# 07_MOTOR.net
KiCad netlist of a schematic drawn in Altium Designer
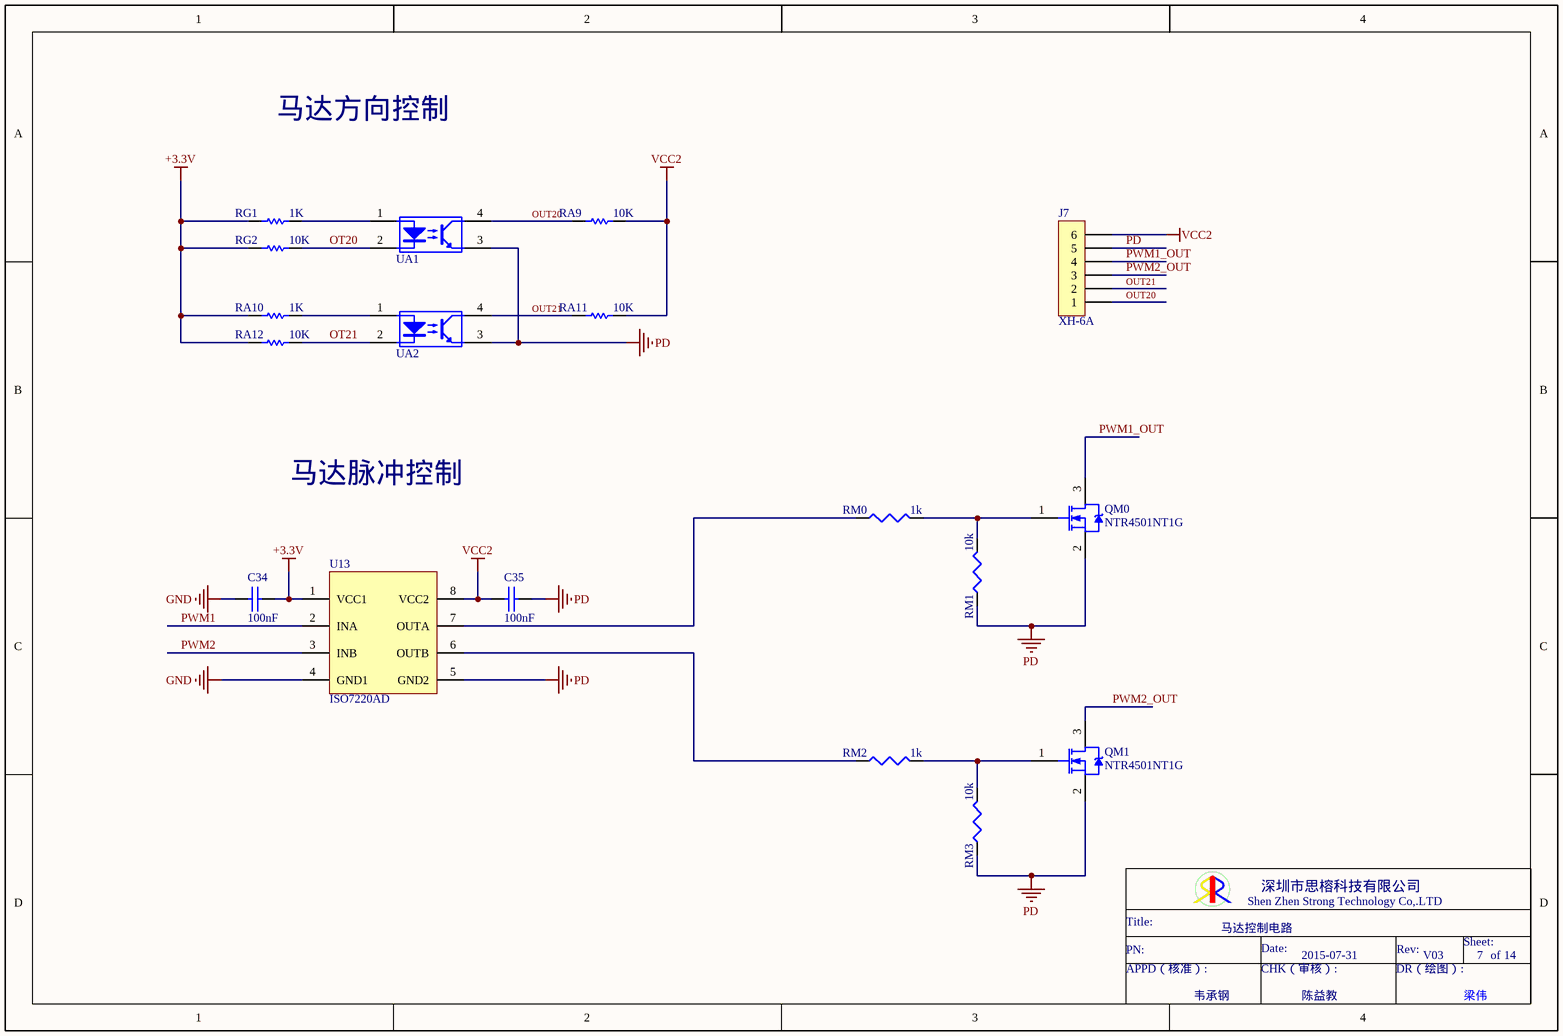
[diagram p0: 07_MOTOR.SchDoc]

(export (version "E")
  (design (tool "Eeschema 10.0.6"))
  (components
    (comp (ref "C34") (value "100nF") (footprint "0603C") (libsource (lib "WeiCHGSCH") (part "CAP")))
    (comp (ref "C35") (value "100nF") (footprint "0603C") (libsource (lib "WeiCHGSCH") (part "CAP")))
    (comp (ref "J7")
      (value "XH-6A")
      (footprint "CN6-2.54")
      (description "单排")
      (libsource (lib "Mylibrary") (part "CON6"))
    )
    (comp (ref "QM0")
      (value "NTR4501NT1G")
      (footprint "SOT23")
      (description "MOSFET N沟道")
      (libsource (lib "LGA") (part "MOSFET-N"))
    )
    (comp (ref "QM1")
      (value "NTR4501NT1G")
      (footprint "SOT23")
      (description "MOSFET N沟道")
      (libsource (lib "LGA") (part "MOSFET-N"))
    )
    (comp (ref "RA9") (value "10K") (footprint "0603R") (libsource (lib "Mylibrary") (part "RES")))
    (comp (ref "RA10") (value "1K") (footprint "0603R") (libsource (lib "Mylibrary") (part "RES")))
    (comp (ref "RA11") (value "10K") (footprint "0603R") (libsource (lib "Mylibrary") (part "RES")))
    (comp (ref "RA12") (value "10K") (footprint "0603R") (libsource (lib "Mylibrary") (part "RES")))
    (comp (ref "RG1") (value "1K") (footprint "0603R") (libsource (lib "Mylibrary") (part "RES")))
    (comp (ref "RG2") (value "10K") (footprint "0603R") (libsource (lib "Mylibrary") (part "RES")))
    (comp (ref "RM0") (value "1k") (footprint "0603R") (libsource (lib "LGA") (part "RES1")))
    (comp (ref "RM1") (value "10k") (footprint "0603R") (libsource (lib "LGA") (part "RES1")))
    (comp (ref "RM2") (value "1k") (footprint "0603R") (libsource (lib "LGA") (part "RES1")))
    (comp (ref "RM3") (value "10k") (footprint "0603R") (libsource (lib "LGA") (part "RES1")))
    (comp (ref "U13")
      (value "ISO7220AD")
      (footprint "SOP8")
      (description "DUAL DIGITAL ISOLATOR")
      (libsource (lib "Mylibrary") (part "ISO7220"))
    )
    (comp (ref "UA1")
      (value "AQY212GS")
      (footprint "SOP4-2.54")
      (libsource (lib "Mylibrary") (part "TLP281"))
    )
    (comp (ref "UA2")
      (value "AQY212GS")
      (footprint "SOP4-2.54")
      (libsource (lib "Mylibrary") (part "TLP281"))
    )
  )
  (nets
    (net (code "1") (name "+3.3V") (class "Default")
      (node (ref "C34") (pin "2") (pinfunction "2_2") (pintype "passive"))
      (node (ref "RA10") (pin "1") (pinfunction "1_1") (pintype "passive"))
      (node (ref "RA12") (pin "1") (pinfunction "1_1") (pintype "passive"))
      (node (ref "RG1") (pin "1") (pinfunction "1_1") (pintype "passive"))
      (node (ref "RG2") (pin "1") (pinfunction "1_1") (pintype "passive"))
      (node (ref "U13") (pin "1") (pinfunction "VCC1_1") (pintype "passive"))
    )
    (net (code "2") (name "/OT20") (class "Default")
      (node (ref "RG2") (pin "2") (pinfunction "2_2") (pintype "passive"))
      (node (ref "UA1") (pin "2") (pinfunction "LED_Cathode_2") (pintype "passive"))
    )
    (net (code "3") (name "/OT21") (class "Default")
      (node (ref "RA12") (pin "2") (pinfunction "2_2") (pintype "passive"))
      (node (ref "UA2") (pin "2") (pinfunction "LED_Cathode_2") (pintype "passive"))
    )
    (net (code "4") (name "/OUT20") (class "Default")
      (node (ref "J7") (pin "1") (pinfunction "1_1") (pintype "passive"))
      (node (ref "RA9") (pin "1") (pinfunction "1_1") (pintype "passive"))
      (node (ref "UA1") (pin "4") (pinfunction "Collector_4") (pintype "passive"))
    )
    (net (code "5") (name "/OUT21") (class "Default")
      (node (ref "J7") (pin "2") (pinfunction "2_2") (pintype "passive"))
      (node (ref "RA11") (pin "1") (pinfunction "1_1") (pintype "passive"))
      (node (ref "UA2") (pin "4") (pinfunction "Collector_4") (pintype "passive"))
    )
    (net (code "6") (name "/PWM1") (class "Default")
      (node (ref "U13") (pin "2") (pinfunction "INA_2") (pintype "passive"))
    )
    (net (code "7") (name "/PWM1_OUT") (class "Default")
      (node (ref "J7") (pin "4") (pinfunction "4_4") (pintype "passive"))
      (node (ref "QM0") (pin "3") (pinfunction "D_3") (pintype "passive"))
    )
    (net (code "8") (name "/PWM2") (class "Default")
      (node (ref "U13") (pin "3") (pinfunction "INB_3") (pintype "passive"))
    )
    (net (code "9") (name "/PWM2_OUT") (class "Default")
      (node (ref "J7") (pin "3") (pinfunction "3_3") (pintype "passive"))
      (node (ref "QM1") (pin "3") (pinfunction "D_3") (pintype "passive"))
    )
    (net (code "10") (name "GND") (class "Default")
      (node (ref "C34") (pin "1") (pinfunction "1_1") (pintype "passive"))
      (node (ref "U13") (pin "4") (pinfunction "GND1_4") (pintype "passive"))
    )
    (net (code "11") (name "Net-(QM0-G)") (class "Default")
      (node (ref "QM0") (pin "1") (pinfunction "G_1") (pintype "passive"))
      (node (ref "RM0") (pin "2") (pinfunction "2_2") (pintype "passive"))
      (node (ref "RM1") (pin "2") (pinfunction "2_2") (pintype "passive"))
    )
    (net (code "12") (name "Net-(QM1-G)") (class "Default")
      (node (ref "QM1") (pin "1") (pinfunction "G_1") (pintype "passive"))
      (node (ref "RM2") (pin "2") (pinfunction "2_2") (pintype "passive"))
      (node (ref "RM3") (pin "2") (pinfunction "2_2") (pintype "passive"))
    )
    (net (code "13") (name "Net-(U13-OUTA)") (class "Default")
      (node (ref "RM0") (pin "1") (pinfunction "1_1") (pintype "passive"))
      (node (ref "U13") (pin "7") (pinfunction "OUTA_7") (pintype "passive"))
    )
    (net (code "14") (name "Net-(U13-OUTB)") (class "Default")
      (node (ref "RM2") (pin "1") (pinfunction "1_1") (pintype "passive"))
      (node (ref "U13") (pin "6") (pinfunction "OUTB_6") (pintype "passive"))
    )
    (net (code "15") (name "Net-(UA1-LED_Anode)") (class "Default")
      (node (ref "RG1") (pin "2") (pinfunction "2_2") (pintype "passive"))
      (node (ref "UA1") (pin "1") (pinfunction "LED_Anode_1") (pintype "passive"))
    )
    (net (code "16") (name "Net-(UA2-LED_Anode)") (class "Default")
      (node (ref "RA10") (pin "2") (pinfunction "2_2") (pintype "passive"))
      (node (ref "UA2") (pin "1") (pinfunction "LED_Anode_1") (pintype "passive"))
    )
    (net (code "17") (name "PD") (class "Default")
      (node (ref "C35") (pin "1") (pinfunction "1_1") (pintype "passive"))
      (node (ref "J7") (pin "5") (pinfunction "5_5") (pintype "passive"))
      (node (ref "QM0") (pin "2") (pinfunction "S_2") (pintype "passive"))
      (node (ref "QM1") (pin "2") (pinfunction "S_2") (pintype "passive"))
      (node (ref "RM1") (pin "1") (pinfunction "1_1") (pintype "passive"))
      (node (ref "RM3") (pin "1") (pinfunction "1_1") (pintype "passive"))
      (node (ref "U13") (pin "5") (pinfunction "GND2_5") (pintype "passive"))
      (node (ref "UA1") (pin "3") (pinfunction "Emitter_3") (pintype "passive"))
      (node (ref "UA2") (pin "3") (pinfunction "Emitter_3") (pintype "passive"))
    )
    (net (code "18") (name "VCC2") (class "Default")
      (node (ref "C35") (pin "2") (pinfunction "2_2") (pintype "passive"))
      (node (ref "J7") (pin "6") (pinfunction "6_6") (pintype "passive"))
      (node (ref "RA11") (pin "2") (pinfunction "2_2") (pintype "passive"))
      (node (ref "RA9") (pin "2") (pinfunction "2_2") (pintype "passive"))
      (node (ref "U13") (pin "8") (pinfunction "VCC2_8") (pintype "passive"))
    )
  )
)
